# Power_In.net
KiCad netlist of a schematic drawn in Altium Designer
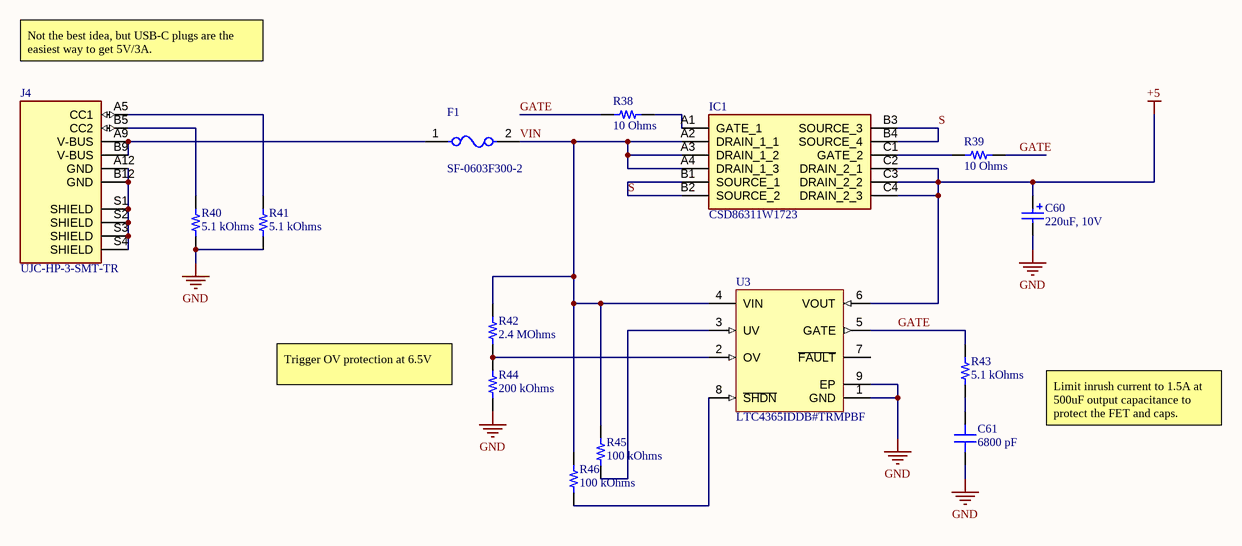
[diagram p0: Power_In.SchDoc]

(export (version "E")
  (design (tool "Eeschema 10.0.6"))
  (components
    (comp (ref "C60")
      (value "220uF, 10V")
      (footprint "WCAP-PSLP_D6.3H5.8")
      (description "WCAP-PSLP Aluminum Polymer Capacitor, V-Chip, SMT, D6.3xH5.8mm, 220uF, 10V")
      (fields
        (field (name "MANUFACTURER PART NUMBER") "875105244013")
        (field (name "MANUFACTURER") "Wurth Elektronik")
      )
      (libsource (lib "Altium_WCAP-PSLP (rev20b)") (part "875105244013"))
    )
    (comp (ref "C61")
      (value "6800 pF")
      (footprint "CAP 0402_1005")
      (description "CAP CER 6800PF 50V X7R 0402")
      (fields
        (field (name "PART NUMBER") "GCM155R71H682KA55D")
        (field (name "MANUFACTURER") "Murata Electronics")
      )
      (libsource (lib "Celestial Altium Library - altium_library") (part "Capacitor"))
    )
    (comp (ref "F1")
      (value "SF-0603F300-2")
      (footprint "FP-SF-0603S-MFG")
      (description "3A AC 32V DC Fuse Board Mount (Cartridge Style Excluded) Surface Mount 0603 (1608 Metric)")
      (fields (field (name "MANUFACTURER") "Bourns Inc."))
      (libsource (lib "Altium Content Vault") (part "5bcf9b9f640e542cf0359d10258e979"))
    )
    (comp (ref "IC1")
      (value "CSD86311W1723")
      (footprint "SamacSys:BGA12C50P4X3_228X170X62")
      (description "Integrated Circuit")
      (fields (field (name "MOUSER PART NUMBER") "595-CSD86311W1723"))
      (libsource (lib "*") (part "CSD86311W1723"))
    )
    (comp (ref "J4")
      (value "UJC-HP-3-SMT-TR")
      (footprint "UJC-HP-3-SMT-TR:CUI_UJC-HP-3-SMT-TR")
      (description "Type C, 3 A, Right Angle, Surface Mount (SMT), Power-Only USB Receptacle")
      (fields (field (name "MF") "{'manufacturer': u'CUI Devices'}"))
      (libsource (lib "*") (part "UJC-HP-3-SMT-TR"))
    )
    (comp (ref "R38")
      (value "10 Ohms")
      (footprint "RES 0402_1005")
      (description "RES 10 OHM 1% 1/8W 0402")
      (fields
        (field (name "PART NUMBER") "CRGP0402F10R")
        (field (name "MANUFACTURER") "TE Connectivity Passive Product")
      )
      (libsource (lib "Celestial Altium Library - altium_library") (part "Resistor"))
    )
    (comp (ref "R39")
      (value "10 Ohms")
      (footprint "RES 0402_1005")
      (description "RES 10 OHM 1% 1/8W 0402")
      (fields
        (field (name "PART NUMBER") "CRGP0402F10R")
        (field (name "MANUFACTURER") "TE Connectivity Passive Product")
      )
      (libsource (lib "Celestial Altium Library - altium_library") (part "Resistor"))
    )
    (comp (ref "R40")
      (value "5.1 kOhms")
      (footprint "RES 0402_1005")
      (description "RES 5.1K OHM 1% 1/10W 0402")
      (fields
        (field (name "PART NUMBER") "RK73H1ETTP5101F")
        (field (name "MANUFACTURER") "KOA Speer Electronics, Inc.")
      )
      (libsource (lib "Celestial Altium Library - altium_library") (part "Resistor"))
    )
    (comp (ref "R41")
      (value "5.1 kOhms")
      (footprint "RES 0402_1005")
      (description "RES 5.1K OHM 1% 1/10W 0402")
      (fields
        (field (name "PART NUMBER") "RK73H1ETTP5101F")
        (field (name "MANUFACTURER") "KOA Speer Electronics, Inc.")
      )
      (libsource (lib "Celestial Altium Library - altium_library") (part "Resistor"))
    )
    (comp (ref "R42")
      (value "2.4 MOhms")
      (footprint "RES 0402_1005")
      (description "RES SMD 2.4M OHM 1% 1/16W 0402")
      (fields (field (name "PART NUMBER") "CRCW04022M40FKED") (field (name "MANUFACTURER") "Vishay Dale"))
      (libsource (lib "Celestial Altium Library - altium_library") (part "Resistor"))
    )
    (comp (ref "R43")
      (value "5.1 kOhms")
      (footprint "RES 0402_1005")
      (description "RES SMD 5.1K OHM 5% 1/10W 0402")
      (fields
        (field (name "PART NUMBER") "ERJ-2GEJ512X")
        (field (name "MANUFACTURER") "Panasonic Electronic Components")
      )
      (libsource (lib "Celestial Altium Library - altium_library") (part "Resistor"))
    )
    (comp (ref "R44")
      (value "200 kOhms")
      (footprint "RES 0402_1005")
      (description "RES 200K OHM 1% 1/16W 0402")
      (fields
        (field (name "PART NUMBER") "RMCF0402FT200K")
        (field (name "MANUFACTURER") "Stackpole Electronics Inc")
      )
      (libsource (lib "Celestial Altium Library - altium_library") (part "Resistor"))
    )
    (comp (ref "R45")
      (value "100 kOhms")
      (footprint "RES 0402_1005")
      (description "RES SMD 100K OHM 5% 1/5W 0402")
      (fields (field (name "PART NUMBER") "RCS0402100KJNED") (field (name "MANUFACTURER") "Vishay Dale"))
      (libsource (lib "Celestial Altium Library - altium_library") (part "Resistor"))
    )
    (comp (ref "R46")
      (value "100 kOhms")
      (footprint "RES 0402_1005")
      (description "RES SMD 100K OHM 5% 1/5W 0402")
      (fields (field (name "PART NUMBER") "RCS0402100KJNED") (field (name "MANUFACTURER") "Vishay Dale"))
      (libsource (lib "Celestial Altium Library - altium_library") (part "Resistor"))
    )
    (comp (ref "U3")
      (value "LTC4365IDDB#TRMPBF")
      (footprint "LT-DDB-8_V")
      (fields (field (name "MANUFACTURER") "Linear Technology"))
      (libsource (lib "Altium Content Vault") (part "LT-LTC4365-DDB-8"))
    )
  )
  (nets
    (net (code "1") (name "+5") (class "Default")
      (node (ref "C60") (pin "1") (pinfunction "P_1") (pintype "passive"))
      (node (ref "IC1") (pin "C2") (pinfunction "DRAIN_2_1_C2") (pintype "passive"))
      (node (ref "IC1") (pin "C3") (pinfunction "DRAIN_2_2_C3") (pintype "passive"))
      (node (ref "IC1") (pin "C4") (pinfunction "DRAIN_2_3_C4") (pintype "passive"))
      (node (ref "U3") (pin "6") (pinfunction "VOUT_6") (pintype "input"))
    )
    (net (code "2") (name "/GATE") (class "Default")
      (node (ref "R38") (pin "1") (pinfunction "1_1") (pintype "passive"))
      (node (ref "R39") (pin "2") (pinfunction "2_2") (pintype "passive"))
      (node (ref "R43") (pin "2") (pinfunction "2_2") (pintype "passive"))
      (node (ref "U3") (pin "5") (pinfunction "GATE_5") (pintype "output"))
    )
    (net (code "3") (name "/S") (class "Default")
      (node (ref "IC1") (pin "B1") (pinfunction "SOURCE_1_B1") (pintype "passive"))
      (node (ref "IC1") (pin "B2") (pinfunction "SOURCE_2_B2") (pintype "passive"))
      (node (ref "IC1") (pin "B3") (pinfunction "SOURCE_3_B3") (pintype "passive"))
      (node (ref "IC1") (pin "B4") (pinfunction "SOURCE_4_B4") (pintype "passive"))
    )
    (net (code "4") (name "/VIN") (class "Default")
      (node (ref "F1") (pin "2") (pinfunction "2_2") (pintype "passive"))
      (node (ref "IC1") (pin "A2") (pinfunction "DRAIN_1_1_A2") (pintype "passive"))
      (node (ref "IC1") (pin "A3") (pinfunction "DRAIN_1_2_A3") (pintype "passive"))
      (node (ref "IC1") (pin "A4") (pinfunction "DRAIN_1_3_A4") (pintype "passive"))
      (node (ref "R42") (pin "2") (pinfunction "2_2") (pintype "passive"))
      (node (ref "R45") (pin "2") (pinfunction "2_2") (pintype "passive"))
      (node (ref "R46") (pin "2") (pinfunction "2_2") (pintype "passive"))
      (node (ref "U3") (pin "4") (pinfunction "VIN_4") (pintype "power_in"))
    )
    (net (code "5") (name "GND") (class "Default")
      (node (ref "C60") (pin "2") (pinfunction "N_2") (pintype "passive"))
      (node (ref "C61") (pin "1") (pinfunction "1_1") (pintype "passive"))
      (node (ref "R40") (pin "1") (pinfunction "1_1") (pintype "passive"))
      (node (ref "R41") (pin "1") (pinfunction "1_1") (pintype "passive"))
      (node (ref "R44") (pin "1") (pinfunction "1_1") (pintype "passive"))
      (node (ref "U3") (pin "1") (pinfunction "GND_1") (pintype "power_in"))
      (node (ref "U3") (pin "9") (pinfunction "EP_9") (pintype "power_in"))
    )
    (net (code "6") (name "Net-(C61-Pad2)") (class "Default")
      (node (ref "C61") (pin "2") (pinfunction "2_2") (pintype "passive"))
      (node (ref "R43") (pin "1") (pinfunction "1_1") (pintype "passive"))
    )
    (net (code "7") (name "Net-(F1-Pad1)") (class "Default")
      (node (ref "F1") (pin "1") (pinfunction "1_1") (pintype "passive"))
      (node (ref "J4") (pin "A9") (pinfunction "V-BUS_A9") (pintype "power_in"))
      (node (ref "J4") (pin "B9") (pinfunction "V-BUS_B9") (pintype "power_in"))
    )
    (net (code "8") (name "Net-(IC1-GATE_1)") (class "Default")
      (node (ref "IC1") (pin "A1") (pinfunction "GATE_1_A1") (pintype "passive"))
      (node (ref "R38") (pin "2") (pinfunction "2_2") (pintype "passive"))
    )
    (net (code "9") (name "Net-(IC1-GATE_2)") (class "Default")
      (node (ref "IC1") (pin "C1") (pinfunction "GATE_2_C1") (pintype "passive"))
      (node (ref "R39") (pin "1") (pinfunction "1_1") (pintype "passive"))
    )
    (net (code "10") (name "Net-(J4-CC1)") (class "Default")
      (node (ref "J4") (pin "A5") (pinfunction "CC1_A5") (pintype "bidirectional"))
      (node (ref "R41") (pin "2") (pinfunction "2_2") (pintype "passive"))
    )
    (net (code "11") (name "Net-(J4-CC2)") (class "Default")
      (node (ref "J4") (pin "B5") (pinfunction "CC2_B5") (pintype "bidirectional"))
      (node (ref "R40") (pin "2") (pinfunction "2_2") (pintype "passive"))
    )
    (net (code "12") (name "Net-(J4-GND-PadA12)") (class "Default")
      (node (ref "J4") (pin "A12") (pinfunction "GND_A12") (pintype "power_in"))
      (node (ref "J4") (pin "B12") (pinfunction "GND_B12") (pintype "power_in"))
      (node (ref "J4") (pin "S1") (pinfunction "SHIELD_S1") (pintype "passive"))
      (node (ref "J4") (pin "S2") (pinfunction "SHIELD_S2") (pintype "passive"))
      (node (ref "J4") (pin "S3") (pinfunction "SHIELD_S3") (pintype "passive"))
      (node (ref "J4") (pin "S4") (pinfunction "SHIELD_S4") (pintype "passive"))
    )
    (net (code "13") (name "Net-(U3-OV)") (class "Default")
      (node (ref "R42") (pin "1") (pinfunction "1_1") (pintype "passive"))
      (node (ref "R44") (pin "2") (pinfunction "2_2") (pintype "passive"))
      (node (ref "U3") (pin "2") (pinfunction "OV_2") (pintype "input"))
    )
    (net (code "14") (name "Net-(U3-UV)") (class "Default")
      (node (ref "R45") (pin "1") (pinfunction "1_1") (pintype "passive"))
      (node (ref "U3") (pin "3") (pinfunction "UV_3") (pintype "input"))
    )
    (net (code "15") (name "Net-(U3-~{SHDN})") (class "Default")
      (node (ref "R46") (pin "1") (pinfunction "1_1") (pintype "passive"))
      (node (ref "U3") (pin "8") (pinfunction "~{SHDN}_8") (pintype "input"))
    )
    (net (code "16") (name "unconnected-(U3-~{FAULT}-Pad7)") (class "Default")
      (node (ref "U3") (pin "7") (pinfunction "~{FAULT}_7") (pintype "open_collector"))
    )
  )
)
